# Mini-Ph0xx_01.net
KiCad netlist of a schematic drawn in Altium Designer
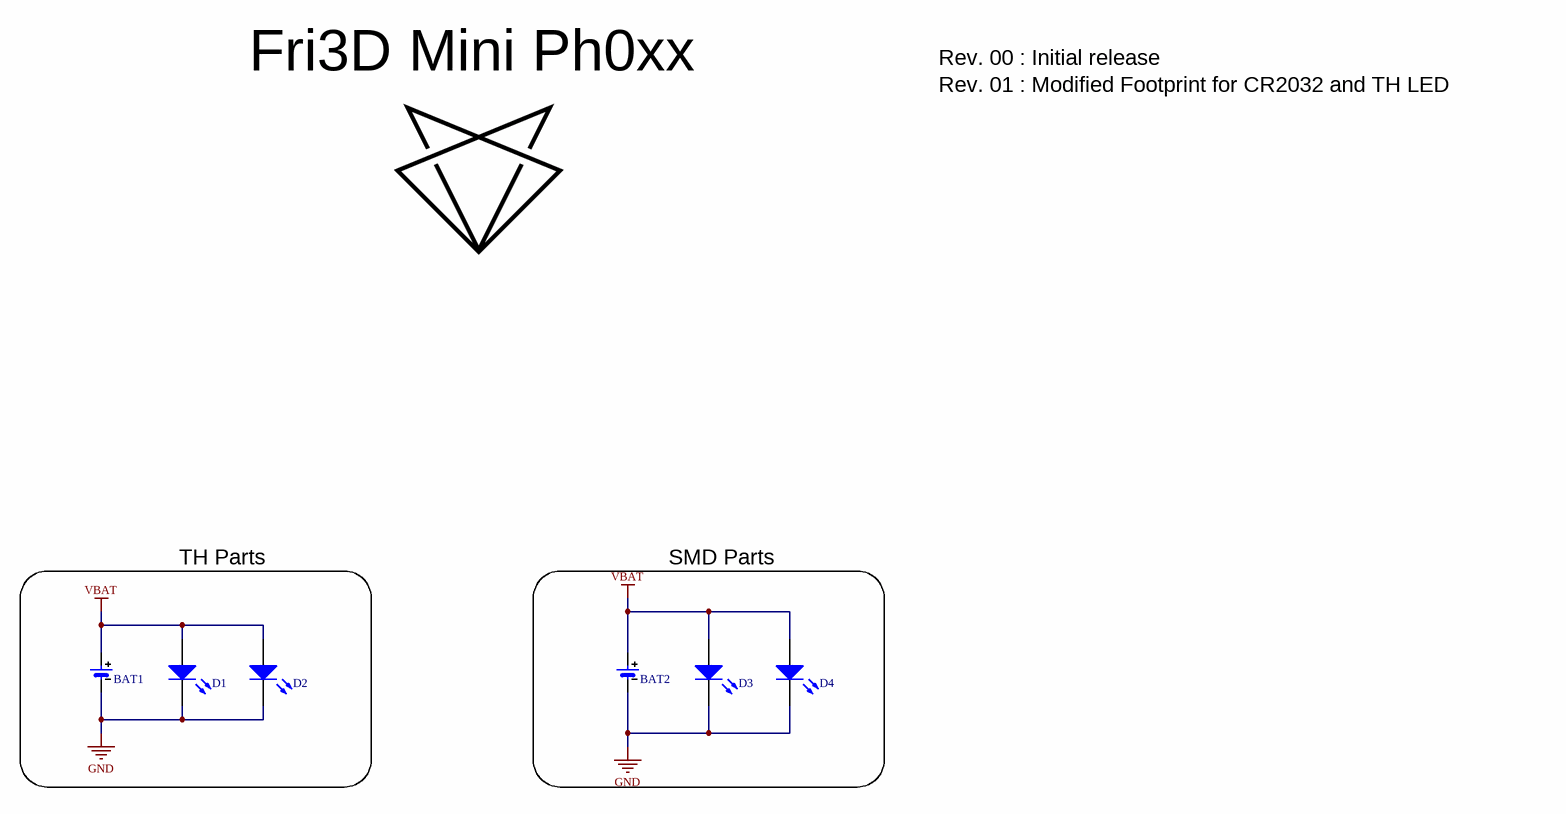
[diagram p0: Mini-Ph0xx_01.SchDoc]

(export (version "E")
  (design (tool "Eeschema 10.0.6"))
  (components
    (comp (ref "BAT1")
      (value "CR2032 Battery Holder")
      (footprint "BAT_CR2032_China")
      (description "=Description")
      (libsource (lib "Phyx_Components") (part "BAT_2"))
    )
    (comp (ref "BAT2")
      (value "CR2032 SMD Battery Holder")
      (footprint "BAT_CR2032_KEY_1060")
      (description "=Description")
      (libsource (lib "Phyx_Components") (part "BAT_2"))
    )
    (comp (ref "D1")
      (value "Default 5mm Blue LED")
      (footprint "LED_5MM_BL")
      (description "=Description")
      (libsource (lib "Phyx_Components") (part "LED_BLUE"))
    )
    (comp (ref "D2")
      (value "Default 5mm Blue LED")
      (footprint "LED_5MM_BL")
      (description "=Description")
      (libsource (lib "Phyx_Components") (part "LED_BLUE"))
    )
    (comp (ref "D3")
      (value "Default 0805 Blue LED")
      (footprint "LED_0805_BL")
      (description "LED # Blue 0805")
      (libsource (lib "Phyx_Components") (part "LED_BLUE"))
    )
    (comp (ref "D4")
      (value "Default 0805 Blue LED")
      (footprint "LED_0805_BL")
      (description "LED # Blue 0805")
      (libsource (lib "Phyx_Components") (part "LED_BLUE"))
    )
  )
  (nets
    (net (code "1") (name "GND") (class "Default")
      (node (ref "BAT1") (pin "2") (pinfunction "2_2") (pintype "passive"))
      (node (ref "BAT2") (pin "2") (pinfunction "2_2") (pintype "passive"))
      (node (ref "D1") (pin "2") (pinfunction "K_2") (pintype "passive"))
      (node (ref "D2") (pin "2") (pinfunction "K_2") (pintype "passive"))
      (node (ref "D3") (pin "2") (pinfunction "K_2") (pintype "passive"))
      (node (ref "D4") (pin "2") (pinfunction "K_2") (pintype "passive"))
    )
    (net (code "2") (name "VBAT") (class "Default")
      (node (ref "BAT1") (pin "1") (pinfunction "1_1") (pintype "passive"))
      (node (ref "BAT2") (pin "1") (pinfunction "1_1") (pintype "passive"))
      (node (ref "D1") (pin "1") (pinfunction "A_1") (pintype "passive"))
      (node (ref "D2") (pin "1") (pinfunction "A_1") (pintype "passive"))
      (node (ref "D3") (pin "1") (pinfunction "A_1") (pintype "passive"))
      (node (ref "D4") (pin "1") (pinfunction "A_1") (pintype "passive"))
    )
  )
)
